# SCH_dial_2026-03-23.net
KiCad netlist of a schematic drawn in EasyEDA
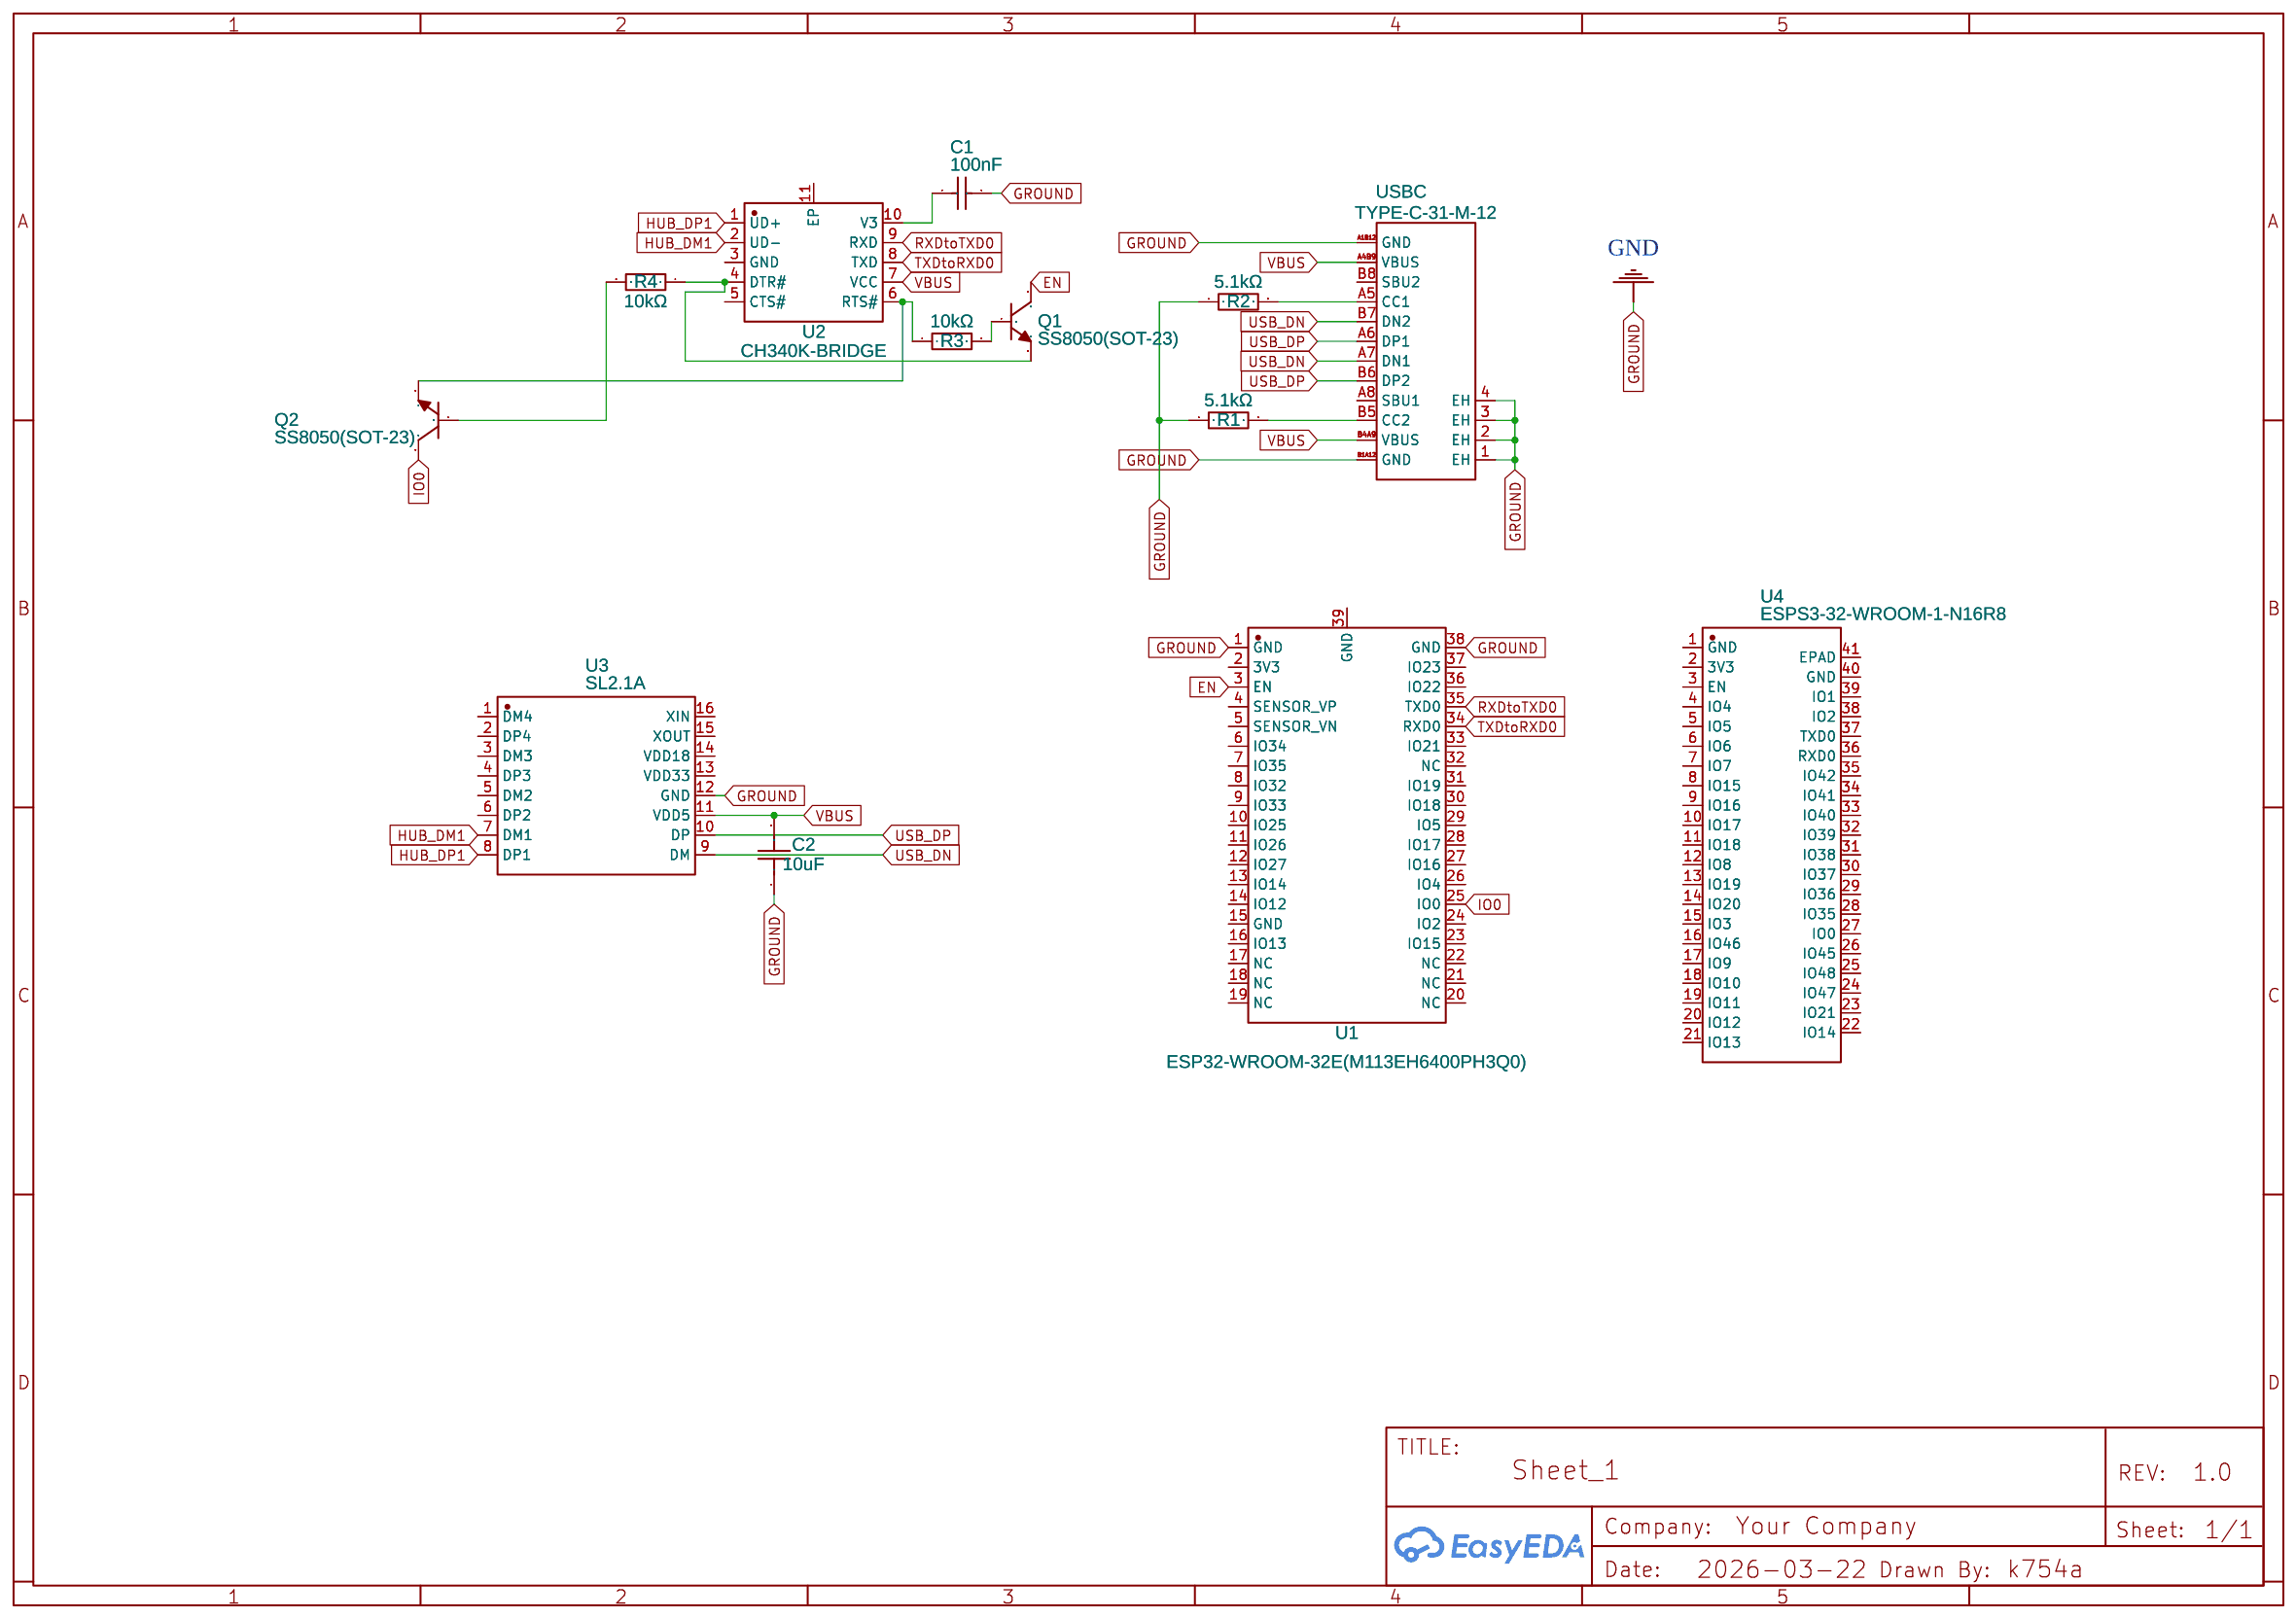
[diagram p0: schematic sheet]

(export (version "E")
  (design (tool "Eeschema 10.0.6"))
  (components
    (comp (ref "C1")
      (value "100nF")
      (fields (field (name "Manufacturer Part") "0.1UF(104) +-20% 63v"))
      (libsource (lib "") (part "100nF"))
    )
    (comp (ref "C2")
      (value "10uF")
      (fields (field (name "Manufacturer Part") "C0603B106M010T") (field (name "Manufacturer") "IHHEC(禾伸堂)"))
      (libsource (lib "") (part "C0603B106M010T"))
    )
    (comp (ref "Q1")
      (value "SS8050(SOT-23)")
      (fields (field (name "Manufacturer") "ALJ(龙晶微)"))
      (libsource (lib "") (part "SS8050(SOT-23)"))
    )
    (comp (ref "Q2")
      (value "SS8050(SOT-23)")
      (fields (field (name "Manufacturer") "ALJ(龙晶微)"))
      (libsource (lib "") (part "SS8050(SOT-23)_1"))
    )
    (comp (ref "R1")
      (value "5.1kΩ")
      (fields (field (name "Manufacturer Part") "RMC06035.1K1%N") (field (name "Manufacturer") "Tyohm(幸亚电阻)"))
      (libsource (lib "") (part "RMC06035.1K1%N"))
    )
    (comp (ref "R2")
      (value "5.1kΩ")
      (fields (field (name "Manufacturer Part") "RMC06035.1K1%N") (field (name "Manufacturer") "Tyohm(幸亚电阻)"))
      (libsource (lib "") (part "RMC06035.1K1%N"))
    )
    (comp (ref "R3")
      (value "10kΩ")
      (fields
        (field (name "Manufacturer Part") "MELF-MFR02041/4WS10KΩFT50")
        (field (name "Manufacturer") "Thunder Component(帝谷)")
      )
      (libsource (lib "") (part "MELF-MFR02041/4WS10KΩFT50"))
    )
    (comp (ref "R4")
      (value "10kΩ")
      (fields
        (field (name "Manufacturer Part") "MELF-MFR02041/4WS10KΩFT50")
        (field (name "Manufacturer") "Thunder Component(帝谷)")
      )
      (libsource (lib "") (part "MELF-MFR02041/4WS10KΩFT50_1"))
    )
    (comp (ref "U1")
      (value "ESP32-WROOM-32E(M113EH6400PH3Q0)")
      (fields (field (name "Manufacturer") "ESPRESSIF(乐鑫)"))
      (libsource (lib "") (part "ESP32-WROOM-32E(M113EH6400PH3Q0)"))
    )
    (comp (ref "U2")
      (value "CH340K-BRIDGE")
      (fields (field (name "Manufacturer Part") "CH340K") (field (name "Manufacturer") "WCH(南京沁恒)"))
      (libsource (lib "") (part "CH340K"))
    )
    (comp (ref "U3")
      (value "SL2.1A")
      (fields (field (name "Manufacturer") "CoreChips(和芯润德)"))
      (libsource (lib "") (part "SL2.1A"))
    )
    (comp (ref "U4") (value "ESPS3-32-WROOM-1-N16R8") (libsource (lib "") (part "ESPS3-32-WROOM-1-N16R8")))
    (comp (ref "USBC")
      (value "TYPE-C-31-M-12")
      (fields (field (name "Manufacturer") "韩国韩荣"))
      (libsource (lib "") (part "TYPE-C-31-M-12"))
    )
  )
  (nets
    (net (code "1") (name "EN") (class "Default")
      (node (ref "Q1") (pin "3") (pinfunction "C_3") (pintype "input"))
      (node (ref "U1") (pin "3") (pinfunction "EN_3") (pintype "unspecified"))
    )
    (net (code "2") (name "GROUND") (class "Default")
      (node (ref "C1") (pin "2") (pinfunction "2_2") (pintype "input"))
      (node (ref "C2") (pin "1") (pinfunction "1_1") (pintype "unspecified"))
      (node (ref "R1") (pin "1") (pinfunction "1_1") (pintype "unspecified"))
      (node (ref "R2") (pin "1") (pinfunction "1_1") (pintype "unspecified"))
      (node (ref "U1") (pin "1") (pinfunction "GND_1") (pintype "unspecified"))
      (node (ref "U1") (pin "38") (pinfunction "GND_38") (pintype "unspecified"))
      (node (ref "U3") (pin "12") (pinfunction "GND_12") (pintype "unspecified"))
      (node (ref "USBC") (pin "1") (pinfunction "EH_1") (pintype "unspecified"))
      (node (ref "USBC") (pin "2") (pinfunction "EH_2") (pintype "unspecified"))
      (node (ref "USBC") (pin "3") (pinfunction "EH_3") (pintype "unspecified"))
      (node (ref "USBC") (pin "4") (pinfunction "EH_4") (pintype "unspecified"))
      (node (ref "USBC") (pin "A1B12") (pinfunction "GND_A1B12") (pintype "unspecified"))
      (node (ref "USBC") (pin "B1A12") (pinfunction "GND_B1A12") (pintype "unspecified"))
    )
    (net (code "3") (name "HUB_DM1") (class "Default")
      (node (ref "U2") (pin "2") (pinfunction "UD-_2") (pintype "unspecified"))
      (node (ref "U3") (pin "7") (pinfunction "DM1_7") (pintype "unspecified"))
    )
    (net (code "4") (name "HUB_DP1") (class "Default")
      (node (ref "U2") (pin "1") (pinfunction "UD+_1") (pintype "unspecified"))
      (node (ref "U3") (pin "8") (pinfunction "DP1_8") (pintype "unspecified"))
    )
    (net (code "5") (name "IO0") (class "Default")
      (node (ref "Q2") (pin "3") (pinfunction "C_3") (pintype "input"))
      (node (ref "U1") (pin "25") (pinfunction "IO0_25") (pintype "unspecified"))
    )
    (net (code "6") (name "Net-(Q1-B)") (class "Default")
      (node (ref "Q1") (pin "1") (pinfunction "B_1") (pintype "input"))
      (node (ref "R3") (pin "2") (pinfunction "2_2") (pintype "unspecified"))
    )
    (net (code "7") (name "Net-(Q1-E)") (class "Default")
      (node (ref "Q1") (pin "2") (pinfunction "E_2") (pintype "input"))
      (node (ref "R4") (pin "1") (pinfunction "1_1") (pintype "unspecified"))
      (node (ref "U2") (pin "4") (pinfunction "DTR#_4") (pintype "unspecified"))
    )
    (net (code "8") (name "Net-(Q2-B)") (class "Default")
      (node (ref "Q2") (pin "1") (pinfunction "B_1") (pintype "input"))
      (node (ref "R4") (pin "2") (pinfunction "2_2") (pintype "unspecified"))
    )
    (net (code "9") (name "Net-(Q2-E)") (class "Default")
      (node (ref "Q2") (pin "2") (pinfunction "E_2") (pintype "input"))
      (node (ref "R3") (pin "1") (pinfunction "1_1") (pintype "unspecified"))
      (node (ref "U2") (pin "6") (pinfunction "RTS#_6") (pintype "unspecified"))
    )
    (net (code "10") (name "Net-(U2-V3)") (class "Default")
      (node (ref "C1") (pin "1") (pinfunction "1_1") (pintype "input"))
      (node (ref "U2") (pin "10") (pinfunction "V3_10") (pintype "unspecified"))
    )
    (net (code "11") (name "Net-(USBC-CC1)") (class "Default")
      (node (ref "R2") (pin "2") (pinfunction "2_2") (pintype "unspecified"))
      (node (ref "USBC") (pin "A5") (pinfunction "CC1_A5") (pintype "unspecified"))
    )
    (net (code "12") (name "Net-(USBC-CC2)") (class "Default")
      (node (ref "R1") (pin "2") (pinfunction "2_2") (pintype "unspecified"))
      (node (ref "USBC") (pin "B5") (pinfunction "CC2_B5") (pintype "unspecified"))
    )
    (net (code "13") (name "RXDtoTXD0") (class "Default")
      (node (ref "U1") (pin "35") (pinfunction "TXD0_35") (pintype "unspecified"))
      (node (ref "U2") (pin "9") (pinfunction "RXD_9") (pintype "unspecified"))
    )
    (net (code "14") (name "TXDtoRXD0") (class "Default")
      (node (ref "U1") (pin "34") (pinfunction "RXD0_34") (pintype "unspecified"))
      (node (ref "U2") (pin "8") (pinfunction "TXD_8") (pintype "unspecified"))
    )
    (net (code "15") (name "USB_DN") (class "Default")
      (node (ref "U3") (pin "9") (pinfunction "DM_9") (pintype "unspecified"))
      (node (ref "USBC") (pin "A7") (pinfunction "DN1_A7") (pintype "unspecified"))
      (node (ref "USBC") (pin "B7") (pinfunction "DN2_B7") (pintype "unspecified"))
    )
    (net (code "16") (name "USB_DP") (class "Default")
      (node (ref "U3") (pin "10") (pinfunction "DP_10") (pintype "unspecified"))
      (node (ref "USBC") (pin "A6") (pinfunction "DP1_A6") (pintype "unspecified"))
      (node (ref "USBC") (pin "B6") (pinfunction "DP2_B6") (pintype "unspecified"))
    )
    (net (code "17") (name "VBUS") (class "Default")
      (node (ref "C2") (pin "2") (pinfunction "2_2") (pintype "unspecified"))
      (node (ref "U2") (pin "7") (pinfunction "VCC_7") (pintype "unspecified"))
      (node (ref "U3") (pin "11") (pinfunction "VDD5_11") (pintype "unspecified"))
      (node (ref "USBC") (pin "A4B9") (pinfunction "VBUS_A4B9") (pintype "unspecified"))
      (node (ref "USBC") (pin "B4A9") (pinfunction "VBUS_B4A9") (pintype "unspecified"))
    )
    (net (code "18") (name "unconnected-(U1-3V3-Pad2)") (class "Default")
      (node (ref "U1") (pin "2") (pinfunction "3V3_2") (pintype "unspecified"))
    )
    (net (code "19") (name "unconnected-(U1-GND-Pad15)") (class "Default")
      (node (ref "U1") (pin "15") (pinfunction "GND_15") (pintype "unspecified"))
    )
    (net (code "20") (name "unconnected-(U1-GND-Pad39)") (class "Default")
      (node (ref "U1") (pin "39") (pinfunction "GND_39") (pintype "unspecified"))
    )
    (net (code "21") (name "unconnected-(U1-IO2-Pad24)") (class "Default")
      (node (ref "U1") (pin "24") (pinfunction "IO2_24") (pintype "unspecified"))
    )
    (net (code "22") (name "unconnected-(U1-IO4-Pad26)") (class "Default")
      (node (ref "U1") (pin "26") (pinfunction "IO4_26") (pintype "unspecified"))
    )
    (net (code "23") (name "unconnected-(U1-IO5-Pad29)") (class "Default")
      (node (ref "U1") (pin "29") (pinfunction "IO5_29") (pintype "unspecified"))
    )
    (net (code "24") (name "unconnected-(U1-IO12-Pad14)") (class "Default")
      (node (ref "U1") (pin "14") (pinfunction "IO12_14") (pintype "unspecified"))
    )
    (net (code "25") (name "unconnected-(U1-IO13-Pad16)") (class "Default")
      (node (ref "U1") (pin "16") (pinfunction "IO13_16") (pintype "unspecified"))
    )
    (net (code "26") (name "unconnected-(U1-IO14-Pad13)") (class "Default")
      (node (ref "U1") (pin "13") (pinfunction "IO14_13") (pintype "unspecified"))
    )
    (net (code "27") (name "unconnected-(U1-IO15-Pad23)") (class "Default")
      (node (ref "U1") (pin "23") (pinfunction "IO15_23") (pintype "unspecified"))
    )
    (net (code "28") (name "unconnected-(U1-IO16-Pad27)") (class "Default")
      (node (ref "U1") (pin "27") (pinfunction "IO16_27") (pintype "unspecified"))
    )
    (net (code "29") (name "unconnected-(U1-IO17-Pad28)") (class "Default")
      (node (ref "U1") (pin "28") (pinfunction "IO17_28") (pintype "unspecified"))
    )
    (net (code "30") (name "unconnected-(U1-IO18-Pad30)") (class "Default")
      (node (ref "U1") (pin "30") (pinfunction "IO18_30") (pintype "unspecified"))
    )
    (net (code "31") (name "unconnected-(U1-IO19-Pad31)") (class "Default")
      (node (ref "U1") (pin "31") (pinfunction "IO19_31") (pintype "unspecified"))
    )
    (net (code "32") (name "unconnected-(U1-IO21-Pad33)") (class "Default")
      (node (ref "U1") (pin "33") (pinfunction "IO21_33") (pintype "unspecified"))
    )
    (net (code "33") (name "unconnected-(U1-IO22-Pad36)") (class "Default")
      (node (ref "U1") (pin "36") (pinfunction "IO22_36") (pintype "unspecified"))
    )
    (net (code "34") (name "unconnected-(U1-IO23-Pad37)") (class "Default")
      (node (ref "U1") (pin "37") (pinfunction "IO23_37") (pintype "unspecified"))
    )
    (net (code "35") (name "unconnected-(U1-IO25-Pad10)") (class "Default")
      (node (ref "U1") (pin "10") (pinfunction "IO25_10") (pintype "unspecified"))
    )
    (net (code "36") (name "unconnected-(U1-IO26-Pad11)") (class "Default")
      (node (ref "U1") (pin "11") (pinfunction "IO26_11") (pintype "unspecified"))
    )
    (net (code "37") (name "unconnected-(U1-IO27-Pad12)") (class "Default")
      (node (ref "U1") (pin "12") (pinfunction "IO27_12") (pintype "unspecified"))
    )
    (net (code "38") (name "unconnected-(U1-IO32-Pad8)") (class "Default")
      (node (ref "U1") (pin "8") (pinfunction "IO32_8") (pintype "unspecified"))
    )
    (net (code "39") (name "unconnected-(U1-IO33-Pad9)") (class "Default")
      (node (ref "U1") (pin "9") (pinfunction "IO33_9") (pintype "unspecified"))
    )
    (net (code "40") (name "unconnected-(U1-IO34-Pad6)") (class "Default")
      (node (ref "U1") (pin "6") (pinfunction "IO34_6") (pintype "unspecified"))
    )
    (net (code "41") (name "unconnected-(U1-IO35-Pad7)") (class "Default")
      (node (ref "U1") (pin "7") (pinfunction "IO35_7") (pintype "unspecified"))
    )
    (net (code "42") (name "unconnected-(U1-NC-Pad17)") (class "Default")
      (node (ref "U1") (pin "17") (pinfunction "NC_17") (pintype "unspecified"))
    )
    (net (code "43") (name "unconnected-(U1-NC-Pad18)") (class "Default")
      (node (ref "U1") (pin "18") (pinfunction "NC_18") (pintype "unspecified"))
    )
    (net (code "44") (name "unconnected-(U1-NC-Pad19)") (class "Default")
      (node (ref "U1") (pin "19") (pinfunction "NC_19") (pintype "unspecified"))
    )
    (net (code "45") (name "unconnected-(U1-NC-Pad20)") (class "Default")
      (node (ref "U1") (pin "20") (pinfunction "NC_20") (pintype "unspecified"))
    )
    (net (code "46") (name "unconnected-(U1-NC-Pad21)") (class "Default")
      (node (ref "U1") (pin "21") (pinfunction "NC_21") (pintype "unspecified"))
    )
    (net (code "47") (name "unconnected-(U1-NC-Pad22)") (class "Default")
      (node (ref "U1") (pin "22") (pinfunction "NC_22") (pintype "unspecified"))
    )
    (net (code "48") (name "unconnected-(U1-NC-Pad32)") (class "Default")
      (node (ref "U1") (pin "32") (pinfunction "NC_32") (pintype "unspecified"))
    )
    (net (code "49") (name "unconnected-(U1-SENSOR_VN-Pad5)") (class "Default")
      (node (ref "U1") (pin "5") (pinfunction "SENSOR_VN_5") (pintype "unspecified"))
    )
    (net (code "50") (name "unconnected-(U1-SENSOR_VP-Pad4)") (class "Default")
      (node (ref "U1") (pin "4") (pinfunction "SENSOR_VP_4") (pintype "unspecified"))
    )
    (net (code "51") (name "unconnected-(U2-CTS#-Pad5)") (class "Default")
      (node (ref "U2") (pin "5") (pinfunction "CTS#_5") (pintype "unspecified"))
    )
    (net (code "52") (name "unconnected-(U2-EP-Pad11)") (class "Default")
      (node (ref "U2") (pin "11") (pinfunction "EP_11") (pintype "unspecified"))
    )
    (net (code "53") (name "unconnected-(U2-GND-Pad3)") (class "Default")
      (node (ref "U2") (pin "3") (pinfunction "GND_3") (pintype "unspecified"))
    )
    (net (code "54") (name "unconnected-(U3-DM2-Pad5)") (class "Default")
      (node (ref "U3") (pin "5") (pinfunction "DM2_5") (pintype "unspecified"))
    )
    (net (code "55") (name "unconnected-(U3-DM3-Pad3)") (class "Default")
      (node (ref "U3") (pin "3") (pinfunction "DM3_3") (pintype "unspecified"))
    )
    (net (code "56") (name "unconnected-(U3-DM4-Pad1)") (class "Default")
      (node (ref "U3") (pin "1") (pinfunction "DM4_1") (pintype "unspecified"))
    )
    (net (code "57") (name "unconnected-(U3-DP2-Pad6)") (class "Default")
      (node (ref "U3") (pin "6") (pinfunction "DP2_6") (pintype "unspecified"))
    )
    (net (code "58") (name "unconnected-(U3-DP3-Pad4)") (class "Default")
      (node (ref "U3") (pin "4") (pinfunction "DP3_4") (pintype "unspecified"))
    )
    (net (code "59") (name "unconnected-(U3-DP4-Pad2)") (class "Default")
      (node (ref "U3") (pin "2") (pinfunction "DP4_2") (pintype "unspecified"))
    )
    (net (code "60") (name "unconnected-(U3-VDD18-Pad14)") (class "Default")
      (node (ref "U3") (pin "14") (pinfunction "VDD18_14") (pintype "unspecified"))
    )
    (net (code "61") (name "unconnected-(U3-VDD33-Pad13)") (class "Default")
      (node (ref "U3") (pin "13") (pinfunction "VDD33_13") (pintype "unspecified"))
    )
    (net (code "62") (name "unconnected-(U3-XIN-Pad16)") (class "Default")
      (node (ref "U3") (pin "16") (pinfunction "XIN_16") (pintype "unspecified"))
    )
    (net (code "63") (name "unconnected-(U3-XOUT-Pad15)") (class "Default")
      (node (ref "U3") (pin "15") (pinfunction "XOUT_15") (pintype "unspecified"))
    )
    (net (code "64") (name "unconnected-(U4-3V3-Pad2)") (class "Default")
      (node (ref "U4") (pin "2") (pinfunction "3V3_2") (pintype "unspecified"))
    )
    (net (code "65") (name "unconnected-(U4-EN-Pad3)") (class "Default")
      (node (ref "U4") (pin "3") (pinfunction "EN_3") (pintype "unspecified"))
    )
    (net (code "66") (name "unconnected-(U4-EPAD-Pad41)") (class "Default")
      (node (ref "U4") (pin "41") (pinfunction "EPAD_41") (pintype "unspecified"))
    )
    (net (code "67") (name "unconnected-(U4-GND-Pad1)") (class "Default")
      (node (ref "U4") (pin "1") (pinfunction "GND_1") (pintype "unspecified"))
    )
    (net (code "68") (name "unconnected-(U4-GND-Pad40)") (class "Default")
      (node (ref "U4") (pin "40") (pinfunction "GND_40") (pintype "unspecified"))
    )
    (net (code "69") (name "unconnected-(U4-IO0-Pad27)") (class "Default")
      (node (ref "U4") (pin "27") (pinfunction "IO0_27") (pintype "unspecified"))
    )
    (net (code "70") (name "unconnected-(U4-IO1-Pad39)") (class "Default")
      (node (ref "U4") (pin "39") (pinfunction "IO1_39") (pintype "unspecified"))
    )
    (net (code "71") (name "unconnected-(U4-IO2-Pad38)") (class "Default")
      (node (ref "U4") (pin "38") (pinfunction "IO2_38") (pintype "unspecified"))
    )
    (net (code "72") (name "unconnected-(U4-IO3-Pad15)") (class "Default")
      (node (ref "U4") (pin "15") (pinfunction "IO3_15") (pintype "unspecified"))
    )
    (net (code "73") (name "unconnected-(U4-IO4-Pad4)") (class "Default")
      (node (ref "U4") (pin "4") (pinfunction "IO4_4") (pintype "unspecified"))
    )
    (net (code "74") (name "unconnected-(U4-IO5-Pad5)") (class "Default")
      (node (ref "U4") (pin "5") (pinfunction "IO5_5") (pintype "unspecified"))
    )
    (net (code "75") (name "unconnected-(U4-IO6-Pad6)") (class "Default")
      (node (ref "U4") (pin "6") (pinfunction "IO6_6") (pintype "unspecified"))
    )
    (net (code "76") (name "unconnected-(U4-IO7-Pad7)") (class "Default")
      (node (ref "U4") (pin "7") (pinfunction "IO7_7") (pintype "unspecified"))
    )
    (net (code "77") (name "unconnected-(U4-IO8-Pad12)") (class "Default")
      (node (ref "U4") (pin "12") (pinfunction "IO8_12") (pintype "unspecified"))
    )
    (net (code "78") (name "unconnected-(U4-IO9-Pad17)") (class "Default")
      (node (ref "U4") (pin "17") (pinfunction "IO9_17") (pintype "unspecified"))
    )
    (net (code "79") (name "unconnected-(U4-IO10-Pad18)") (class "Default")
      (node (ref "U4") (pin "18") (pinfunction "IO10_18") (pintype "unspecified"))
    )
    (net (code "80") (name "unconnected-(U4-IO11-Pad19)") (class "Default")
      (node (ref "U4") (pin "19") (pinfunction "IO11_19") (pintype "unspecified"))
    )
    (net (code "81") (name "unconnected-(U4-IO12-Pad20)") (class "Default")
      (node (ref "U4") (pin "20") (pinfunction "IO12_20") (pintype "unspecified"))
    )
    (net (code "82") (name "unconnected-(U4-IO13-Pad21)") (class "Default")
      (node (ref "U4") (pin "21") (pinfunction "IO13_21") (pintype "unspecified"))
    )
    (net (code "83") (name "unconnected-(U4-IO14-Pad22)") (class "Default")
      (node (ref "U4") (pin "22") (pinfunction "IO14_22") (pintype "unspecified"))
    )
    (net (code "84") (name "unconnected-(U4-IO15-Pad8)") (class "Default")
      (node (ref "U4") (pin "8") (pinfunction "IO15_8") (pintype "unspecified"))
    )
    (net (code "85") (name "unconnected-(U4-IO16-Pad9)") (class "Default")
      (node (ref "U4") (pin "9") (pinfunction "IO16_9") (pintype "unspecified"))
    )
    (net (code "86") (name "unconnected-(U4-IO17-Pad10)") (class "Default")
      (node (ref "U4") (pin "10") (pinfunction "IO17_10") (pintype "unspecified"))
    )
    (net (code "87") (name "unconnected-(U4-IO18-Pad11)") (class "Default")
      (node (ref "U4") (pin "11") (pinfunction "IO18_11") (pintype "unspecified"))
    )
    (net (code "88") (name "unconnected-(U4-IO19-Pad13)") (class "Default")
      (node (ref "U4") (pin "13") (pinfunction "IO19_13") (pintype "unspecified"))
    )
    (net (code "89") (name "unconnected-(U4-IO20-Pad14)") (class "Default")
      (node (ref "U4") (pin "14") (pinfunction "IO20_14") (pintype "unspecified"))
    )
    (net (code "90") (name "unconnected-(U4-IO21-Pad23)") (class "Default")
      (node (ref "U4") (pin "23") (pinfunction "IO21_23") (pintype "unspecified"))
    )
    (net (code "91") (name "unconnected-(U4-IO35-Pad28)") (class "Default")
      (node (ref "U4") (pin "28") (pinfunction "IO35_28") (pintype "unspecified"))
    )
    (net (code "92") (name "unconnected-(U4-IO36-Pad29)") (class "Default")
      (node (ref "U4") (pin "29") (pinfunction "IO36_29") (pintype "unspecified"))
    )
    (net (code "93") (name "unconnected-(U4-IO37-Pad30)") (class "Default")
      (node (ref "U4") (pin "30") (pinfunction "IO37_30") (pintype "unspecified"))
    )
    (net (code "94") (name "unconnected-(U4-IO38-Pad31)") (class "Default")
      (node (ref "U4") (pin "31") (pinfunction "IO38_31") (pintype "unspecified"))
    )
    (net (code "95") (name "unconnected-(U4-IO39-Pad32)") (class "Default")
      (node (ref "U4") (pin "32") (pinfunction "IO39_32") (pintype "unspecified"))
    )
    (net (code "96") (name "unconnected-(U4-IO40-Pad33)") (class "Default")
      (node (ref "U4") (pin "33") (pinfunction "IO40_33") (pintype "unspecified"))
    )
    (net (code "97") (name "unconnected-(U4-IO41-Pad34)") (class "Default")
      (node (ref "U4") (pin "34") (pinfunction "IO41_34") (pintype "unspecified"))
    )
    (net (code "98") (name "unconnected-(U4-IO42-Pad35)") (class "Default")
      (node (ref "U4") (pin "35") (pinfunction "IO42_35") (pintype "unspecified"))
    )
    (net (code "99") (name "unconnected-(U4-IO45-Pad26)") (class "Default")
      (node (ref "U4") (pin "26") (pinfunction "IO45_26") (pintype "unspecified"))
    )
    (net (code "100") (name "unconnected-(U4-IO46-Pad16)") (class "Default")
      (node (ref "U4") (pin "16") (pinfunction "IO46_16") (pintype "unspecified"))
    )
    (net (code "101") (name "unconnected-(U4-IO47-Pad24)") (class "Default")
      (node (ref "U4") (pin "24") (pinfunction "IO47_24") (pintype "unspecified"))
    )
    (net (code "102") (name "unconnected-(U4-IO48-Pad25)") (class "Default")
      (node (ref "U4") (pin "25") (pinfunction "IO48_25") (pintype "unspecified"))
    )
    (net (code "103") (name "unconnected-(U4-RXD0-Pad36)") (class "Default")
      (node (ref "U4") (pin "36") (pinfunction "RXD0_36") (pintype "unspecified"))
    )
    (net (code "104") (name "unconnected-(U4-TXD0-Pad37)") (class "Default")
      (node (ref "U4") (pin "37") (pinfunction "TXD0_37") (pintype "unspecified"))
    )
    (net (code "105") (name "unconnected-(USBC-SBU1-PadA8)") (class "Default")
      (node (ref "USBC") (pin "A8") (pinfunction "SBU1_A8") (pintype "unspecified"))
    )
    (net (code "106") (name "unconnected-(USBC-SBU2-PadB8)") (class "Default")
      (node (ref "USBC") (pin "B8") (pinfunction "SBU2_B8") (pintype "unspecified"))
    )
  )
)
